# RP_ComputeModule3_rev_3_0_uSDCard.net
KiCad netlist of a schematic drawn in Altium Designer
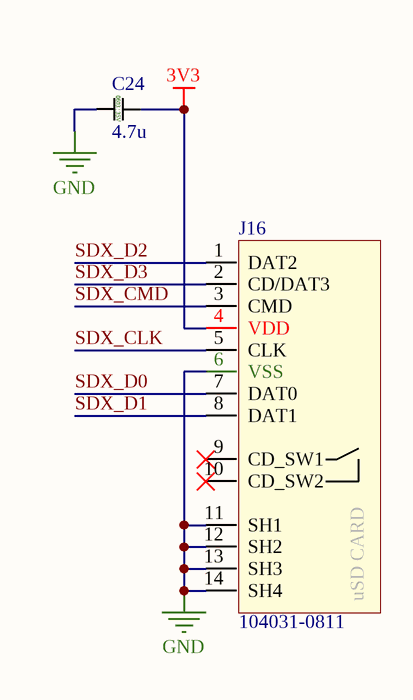
[diagram p0: RP_ComputeModule3_rev.3.0_uSDCard.SchDoc]

(export (version "E")
  (design (tool "Eeschema 10.0.6"))
  (components
    (comp (ref "C24")
      (value "4.7u")
      (footprint "0603 Murata")
      (description "4.7µF 35V Ceramic Capacitor X5R 0603 (1608 Metric) 0.063\" L x 0.031\" W (1.60mm x 0.80mm)")
      (fields
        (field (name "MANUFACTURER") "Murata")
        (field (name "MANUFACTURER PART NUMBER") "GRT188R6YA475KE13D")
      )
      (libsource (lib "Murata_Capacitors") (part "GRT188R6YA475KE13D"))
    )
    (comp (ref "J16")
      (value "104031-0811")
      (footprint "MOLEX 104031-0811")
      (description "CONN MICRO SD CARD PUSH-PULL R/A")
      (fields (field (name "MANUFACTURER") "Molex"))
      (libsource (lib "Molex_Library") (part "104031-0811"))
    )
  )
  (nets
    (net (code "1") (name "/SDX_CLK") (class "Default")
      (node (ref "J16") (pin "5") (pinfunction "CLK_5") (pintype "passive"))
    )
    (net (code "2") (name "/SDX_CMD") (class "Default")
      (node (ref "J16") (pin "3") (pinfunction "CMD_3") (pintype "passive"))
    )
    (net (code "3") (name "/SDX_D0") (class "Default")
      (node (ref "J16") (pin "7") (pinfunction "DAT0_7") (pintype "passive"))
    )
    (net (code "4") (name "/SDX_D1") (class "Default")
      (node (ref "J16") (pin "8") (pinfunction "DAT1_8") (pintype "passive"))
    )
    (net (code "5") (name "/SDX_D2") (class "Default")
      (node (ref "J16") (pin "1") (pinfunction "DAT2_1") (pintype "passive"))
    )
    (net (code "6") (name "/SDX_D3") (class "Default")
      (node (ref "J16") (pin "2") (pinfunction "CD/DAT3_2") (pintype "passive"))
    )
    (net (code "7") (name "3V3") (class "Default")
      (node (ref "C24") (pin "2") (pinfunction "2_2") (pintype "passive"))
      (node (ref "J16") (pin "4") (pinfunction "VDD_4") (pintype "passive"))
    )
    (net (code "8") (name "GND") (class "Default")
      (node (ref "C24") (pin "1") (pinfunction "1_1") (pintype "passive"))
      (node (ref "J16") (pin "11") (pinfunction "SH1_11") (pintype "passive"))
      (node (ref "J16") (pin "12") (pinfunction "SH2_12") (pintype "passive"))
      (node (ref "J16") (pin "13") (pinfunction "SH3_13") (pintype "passive"))
      (node (ref "J16") (pin "14") (pinfunction "SH4_14") (pintype "passive"))
      (node (ref "J16") (pin "6") (pinfunction "VSS_6") (pintype "passive"))
    )
    (net (code "9") (name "unconnected-(J16-CD_SW1-Pad9)") (class "Default")
      (node (ref "J16") (pin "9") (pinfunction "CD_SW1_9") (pintype "passive+no_connect"))
    )
    (net (code "10") (name "unconnected-(J16-CD_SW2-Pad10)") (class "Default")
      (node (ref "J16") (pin "10") (pinfunction "CD_SW2_10") (pintype "passive+no_connect"))
    )
  )
)
